# Sensor.net
KiCad netlist of a schematic drawn in Altium Designer
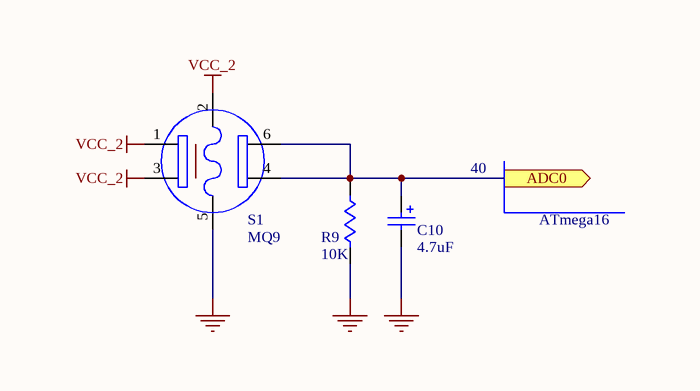
[diagram p0: Sensor.SchDoc]

(export (version "E")
  (design (tool "Eeschema 10.0.6"))
  (components
    (comp (ref "C10")
      (value "4.7uF")
      (footprint "RB_3.175mm")
      (description "Polarized Capacitor (Radial)")
      (fields
        (field (name "MANUFACTURER") "Generic Components")
        (field (name "Comment") "Capacitor_1")
        (field (name "PUBLISHER") "Altium Limited")
      )
      (libsource (lib "my Libraries") (part "Capacitor_1"))
    )
    (comp (ref "R9")
      (value "10K")
      (footprint "AXIAL0.4")
      (description "Resistor")
      (fields (field (name "MANUFACTURER") "Generic Components") (field (name "PUBLISHER") "Altium Limited"))
      (libsource (lib "my Libraries") (part "Resistor"))
    )
    (comp (ref "S1")
      (value "MQ9")
      (footprint "MQ")
      (description "Gas Sensor")
      (fields
        (field (name "MANUFACTURER") "Generic Components")
        (field (name "Comment") "MQ")
        (field (name "PUBLISHER") "Altium Limited")
      )
      (libsource (lib "my Libraries") (part "MQ"))
    )
  )
  (nets
    (net (code "1") (name "/ADC0") (class "Default")
      (node (ref "C10") (pin "1") (pinfunction "1_1") (pintype "passive"))
      (node (ref "R9") (pin "1") (pinfunction "1_1") (pintype "passive"))
      (node (ref "S1") (pin "4") (pinfunction "33_4") (pintype "passive"))
      (node (ref "S1") (pin "6") (pinfunction "6_6") (pintype "passive"))
    )
    (net (code "2") (name "GND") (class "Default")
      (node (ref "C10") (pin "2") (pinfunction "2_2") (pintype "passive"))
      (node (ref "R9") (pin "2") (pinfunction "2_2") (pintype "passive"))
      (node (ref "S1") (pin "5") (pinfunction "5_5") (pintype "passive"))
    )
    (net (code "3") (name "VCC_2") (class "Default")
      (node (ref "S1") (pin "1") (pinfunction "31_1") (pintype "passive"))
      (node (ref "S1") (pin "2") (pinfunction "2_2") (pintype "passive"))
      (node (ref "S1") (pin "3") (pinfunction "3_3") (pintype "passive"))
    )
  )
)
